# pan_tilt_laser_driver.net
KiCad netlist of a schematic drawn in EAGLE
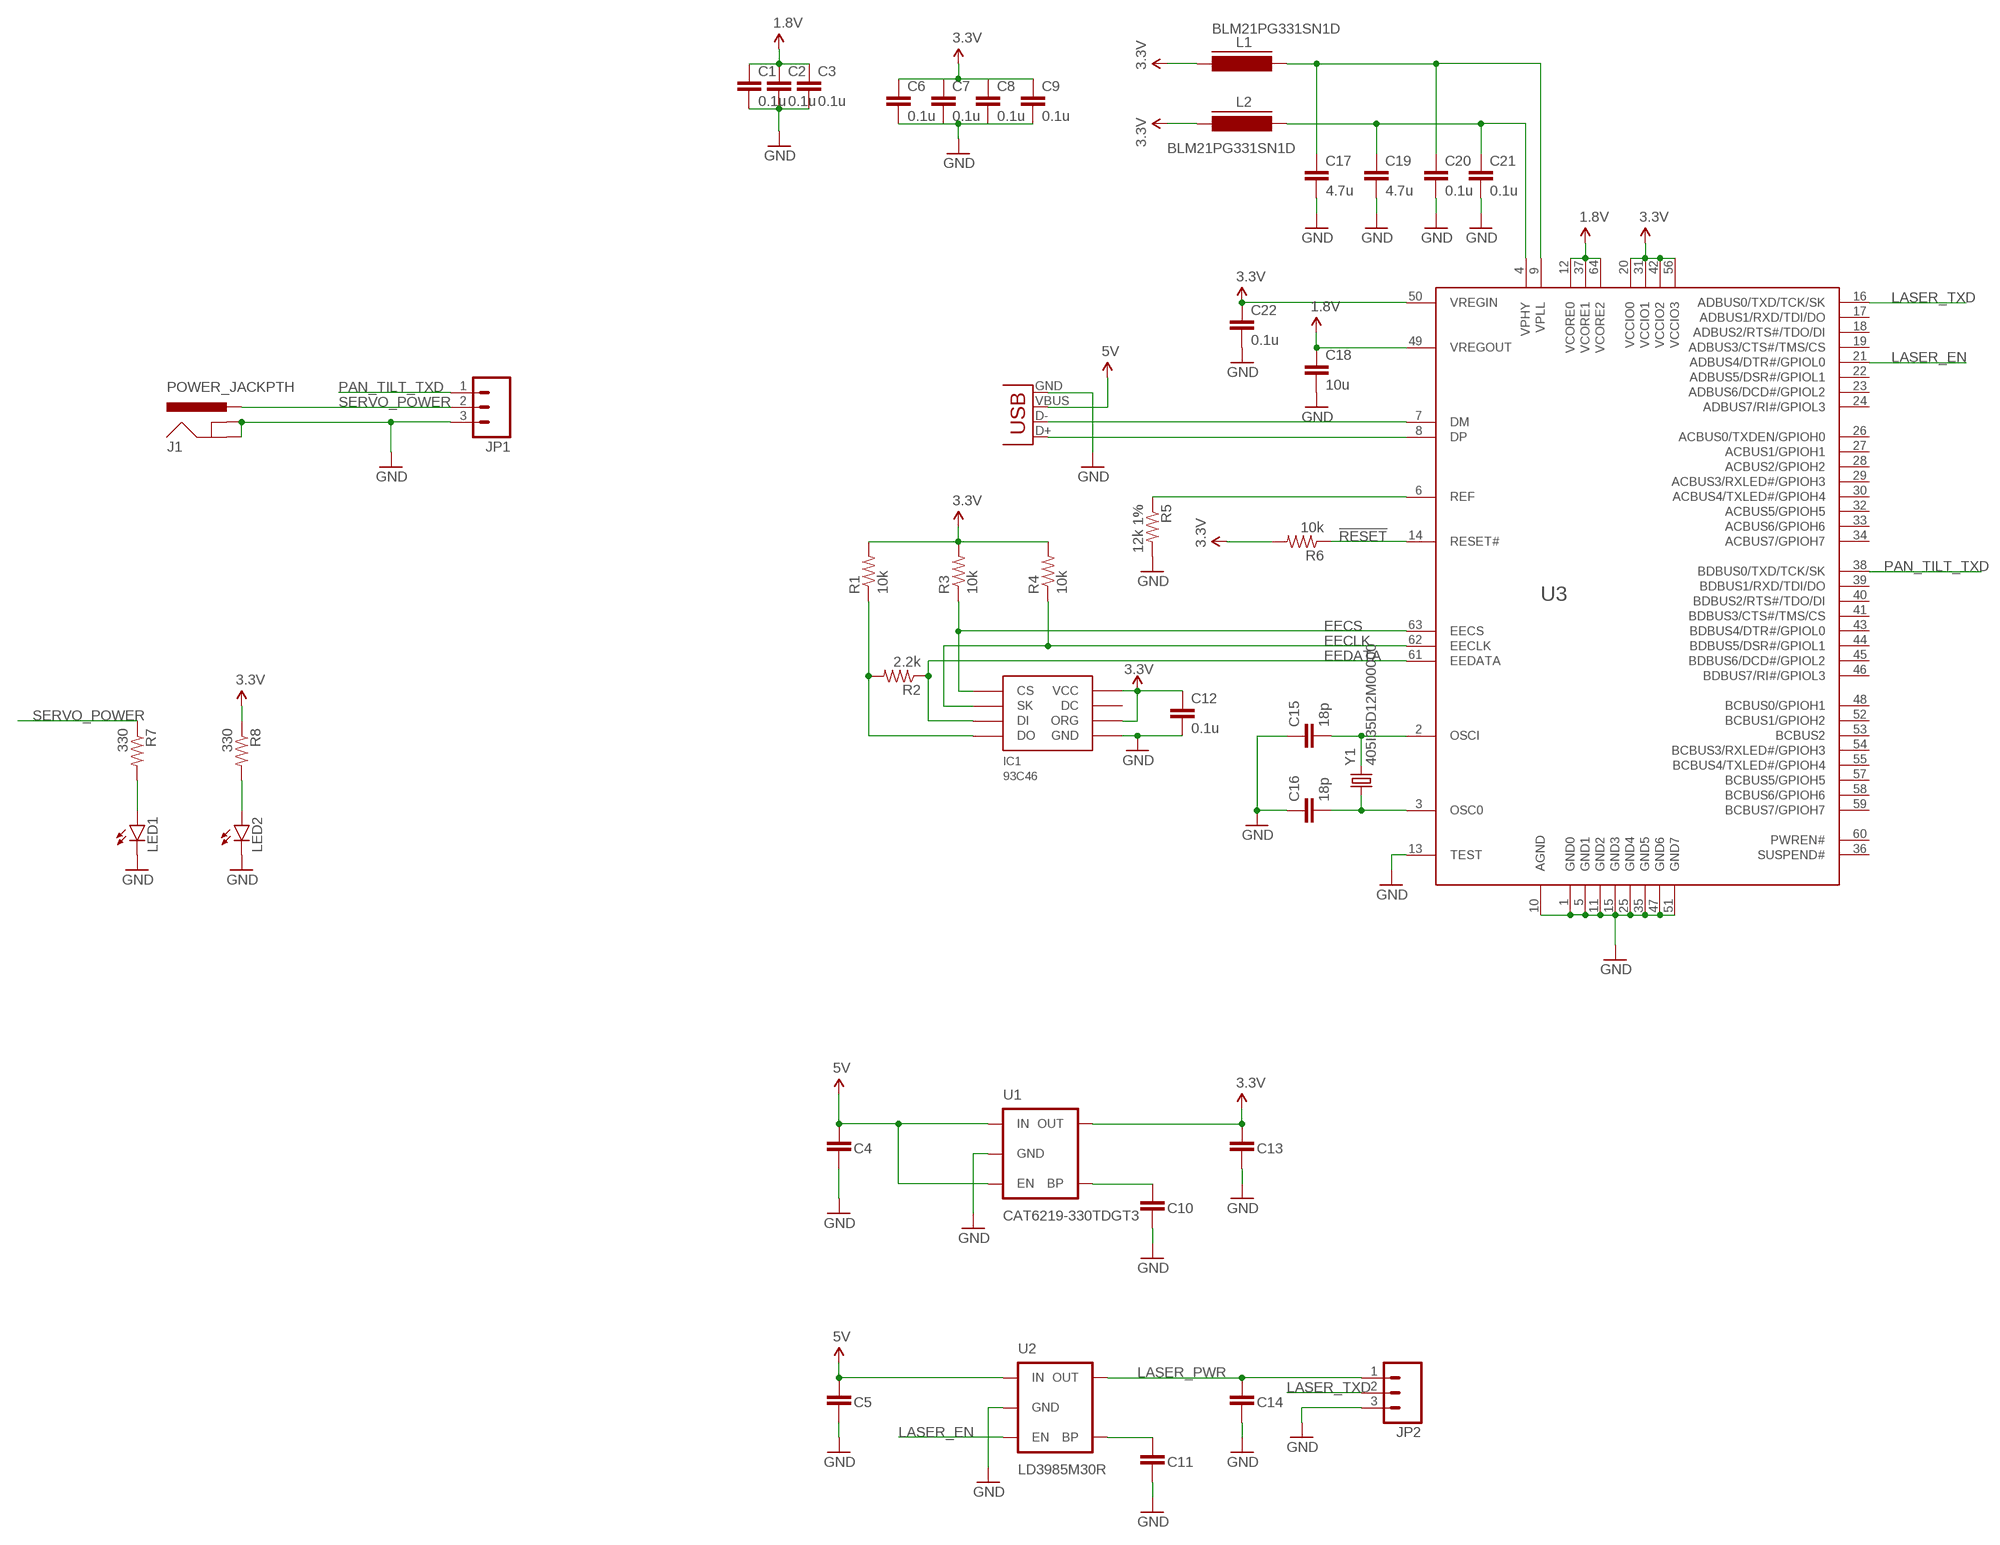
[diagram p0: schematic, sheet 1]

(export (version "E")
  (design (tool "Eeschema 10.0.6"))
  (components
    (comp (ref "C1")
      (value "0.1u")
      (footprint "eagle-import:C0603K")
      (libsource (lib "eagle-import") (part "C-EUC0603K"))
    )
    (comp (ref "C2")
      (value "0.1u")
      (footprint "eagle-import:C0603K")
      (libsource (lib "eagle-import") (part "C-EUC0603K"))
    )
    (comp (ref "C3")
      (value "0.1u")
      (footprint "eagle-import:C0603K")
      (libsource (lib "eagle-import") (part "C-EUC0603K"))
    )
    (comp (ref "C4")
      (value "10u")
      (footprint "eagle-import:0603-CAP")
      (libsource (lib "eagle-import") (part "CAP0603-CAP"))
    )
    (comp (ref "C5")
      (value "10u")
      (footprint "eagle-import:0603-CAP")
      (libsource (lib "eagle-import") (part "CAP0603-CAP"))
    )
    (comp (ref "C6")
      (value "0.1u")
      (footprint "eagle-import:C0603K")
      (libsource (lib "eagle-import") (part "C-EUC0603K"))
    )
    (comp (ref "C7")
      (value "0.1u")
      (footprint "eagle-import:C0603K")
      (libsource (lib "eagle-import") (part "C-EUC0603K"))
    )
    (comp (ref "C8")
      (value "0.1u")
      (footprint "eagle-import:C0603K")
      (libsource (lib "eagle-import") (part "C-EUC0603K"))
    )
    (comp (ref "C9")
      (value "0.1u")
      (footprint "eagle-import:C0603K")
      (libsource (lib "eagle-import") (part "C-EUC0603K"))
    )
    (comp (ref "C10")
      (value "0.01u")
      (footprint "eagle-import:0603-CAP")
      (libsource (lib "eagle-import") (part "CAP0603-CAP"))
    )
    (comp (ref "C11")
      (value "0.01u")
      (footprint "eagle-import:0603-CAP")
      (libsource (lib "eagle-import") (part "CAP0603-CAP"))
    )
    (comp (ref "C12")
      (value "0.1u")
      (footprint "eagle-import:C0603K")
      (libsource (lib "eagle-import") (part "C-EUC0603K"))
    )
    (comp (ref "C13")
      (value "10u")
      (footprint "eagle-import:0603-CAP")
      (libsource (lib "eagle-import") (part "CAP0603-CAP"))
    )
    (comp (ref "C14")
      (value "10u")
      (footprint "eagle-import:0603-CAP")
      (libsource (lib "eagle-import") (part "CAP0603-CAP"))
    )
    (comp (ref "C15")
      (value "18p")
      (footprint "eagle-import:C0603K")
      (libsource (lib "eagle-import") (part "C-EUC0603K"))
    )
    (comp (ref "C16")
      (value "18p")
      (footprint "eagle-import:C0603K")
      (libsource (lib "eagle-import") (part "C-EUC0603K"))
    )
    (comp (ref "C17")
      (value "4.7u")
      (footprint "eagle-import:C0603K")
      (libsource (lib "eagle-import") (part "C-EUC0603K"))
    )
    (comp (ref "C18")
      (value "10u")
      (footprint "eagle-import:C0603K")
      (libsource (lib "eagle-import") (part "C-EUC0603K"))
    )
    (comp (ref "C19")
      (value "4.7u")
      (footprint "eagle-import:C0603K")
      (libsource (lib "eagle-import") (part "C-EUC0603K"))
    )
    (comp (ref "C20")
      (value "0.1u")
      (footprint "eagle-import:C0603K")
      (libsource (lib "eagle-import") (part "C-EUC0603K"))
    )
    (comp (ref "C21")
      (value "0.1u")
      (footprint "eagle-import:C0603K")
      (libsource (lib "eagle-import") (part "C-EUC0603K"))
    )
    (comp (ref "C22")
      (value "0.1u")
      (footprint "eagle-import:C0603K")
      (libsource (lib "eagle-import") (part "C-EUC0603K"))
    )
    (comp (ref "IC1")
      (value "93C46")
      (footprint "eagle-import:SOIC8")
      (libsource (lib "eagle-import") (part "93C46"))
    )
    (comp (ref "J1")
      (value "POWER_JACKPTH")
      (footprint "eagle-import:POWER_JACK_PTH")
      (libsource (lib "eagle-import") (part "POWER_JACKPTH"))
    )
    (comp (ref "JP1")
      (value "M0322-03-5035")
      (footprint "eagle-import:22-03-5035")
      (libsource (lib "eagle-import") (part "M0322-03-5035"))
    )
    (comp (ref "JP2")
      (value "651-5442251")
      (footprint "eagle-import:SCREWTERMINAL-3.5MM-3")
      (libsource (lib "eagle-import") (part "M03SCREW"))
    )
    (comp (ref "L1")
      (value "BLM21PG331SN1D")
      (footprint "eagle-import:FB805")
      (libsource (lib "eagle-import") (part "FERRITE_BEAD805"))
    )
    (comp (ref "L2")
      (value "BLM21PG331SN1D")
      (footprint "eagle-import:FB805")
      (libsource (lib "eagle-import") (part "FERRITE_BEAD805"))
    )
    (comp (ref "LED1")
      (value "LED1206")
      (footprint "eagle-import:LED-1206")
      (libsource (lib "eagle-import") (part "LED1206"))
    )
    (comp (ref "LED2")
      (value "LED1206")
      (footprint "eagle-import:LED-1206")
      (libsource (lib "eagle-import") (part "LED1206"))
    )
    (comp (ref "R1")
      (value "10k")
      (footprint "eagle-import:R0603")
      (libsource (lib "eagle-import") (part "R-US_R0603"))
    )
    (comp (ref "R2")
      (value "2.2k")
      (footprint "eagle-import:R0603")
      (libsource (lib "eagle-import") (part "R-US_R0603"))
    )
    (comp (ref "R3")
      (value "10k")
      (footprint "eagle-import:R0603")
      (libsource (lib "eagle-import") (part "R-US_R0603"))
    )
    (comp (ref "R4")
      (value "10k")
      (footprint "eagle-import:R0603")
      (libsource (lib "eagle-import") (part "R-US_R0603"))
    )
    (comp (ref "R5")
      (value "12k 1%")
      (footprint "eagle-import:R0603")
      (libsource (lib "eagle-import") (part "R-US_R0603"))
    )
    (comp (ref "R6")
      (value "10k")
      (footprint "eagle-import:R0603")
      (libsource (lib "eagle-import") (part "R-US_R0603"))
    )
    (comp (ref "R7")
      (value "330")
      (footprint "eagle-import:R0603")
      (libsource (lib "eagle-import") (part "R-US_R0603"))
    )
    (comp (ref "R8")
      (value "330")
      (footprint "eagle-import:R0603")
      (libsource (lib "eagle-import") (part "R-US_R0603"))
    )
    (comp (ref "U1")
      (value "CAT6219-330TDGT3")
      (footprint "eagle-import:SOT23-5")
      (libsource (lib "eagle-import") (part "V_REG_MIC52195V"))
    )
    (comp (ref "U2")
      (value "LD3985M30R")
      (footprint "eagle-import:SOT23-5")
      (libsource (lib "eagle-import") (part "V_REG_MIC52195V"))
    )
    (comp (ref "U3")
      (value "FT2232H")
      (footprint "eagle-import:LQFP64")
      (libsource (lib "eagle-import") (part "FT2232H"))
    )
    (comp (ref "X1")
      (value "538-47346-0001")
      (footprint "eagle-import:USB-MICROB")
      (libsource (lib "eagle-import") (part "USB-MICROB"))
    )
    (comp (ref "Y1")
      (value "405I35D12M00000")
      (footprint "eagle-import:CRYSTAL-SMD-5X3")
      (libsource (lib "eagle-import") (part "CRYSTAL5X3"))
    )
  )
  (nets
    (net (code "1") (name "/EECLK") (class "Default")
      (node (ref "IC1") (pin "2") (pinfunction "SK_2") (pintype "bidirectional"))
      (node (ref "R4") (pin "1") (pinfunction "1_1") (pintype "passive"))
      (node (ref "U3") (pin "62") (pinfunction "EECLK_62") (pintype "bidirectional"))
    )
    (net (code "2") (name "/EECS") (class "Default")
      (node (ref "IC1") (pin "1") (pinfunction "CS_1") (pintype "bidirectional"))
      (node (ref "R3") (pin "1") (pinfunction "1_1") (pintype "passive"))
      (node (ref "U3") (pin "63") (pinfunction "EECS_63") (pintype "bidirectional"))
    )
    (net (code "3") (name "/EEDATA") (class "Default")
      (node (ref "IC1") (pin "3") (pinfunction "DI_3") (pintype "bidirectional"))
      (node (ref "R2") (pin "1") (pinfunction "1_1") (pintype "passive"))
      (node (ref "U3") (pin "61") (pinfunction "EEDATA_61") (pintype "bidirectional"))
    )
    (net (code "4") (name "/LASER_EN") (class "Default")
      (node (ref "U2") (pin "3") (pinfunction "EN_3") (pintype "input"))
      (node (ref "U3") (pin "21") (pinfunction "ADBUS4/DTR#/GPIOL0_21") (pintype "bidirectional"))
    )
    (net (code "5") (name "/LASER_PWR") (class "Default")
      (node (ref "C14") (pin "1") (pinfunction "1_1") (pintype "passive"))
      (node (ref "JP2") (pin "1") (pinfunction "1_1") (pintype "passive"))
      (node (ref "U2") (pin "5") (pinfunction "OUT_5") (pintype "passive"))
    )
    (net (code "6") (name "/LASER_TXD") (class "Default")
      (node (ref "JP2") (pin "2") (pinfunction "2_2") (pintype "passive"))
      (node (ref "U3") (pin "16") (pinfunction "ADBUS0/TXD/TCK/SK_16") (pintype "bidirectional"))
    )
    (net (code "7") (name "/PAN_TILT_TXD") (class "Default")
      (node (ref "JP1") (pin "1") (pinfunction "1_1") (pintype "passive"))
      (node (ref "U3") (pin "38") (pinfunction "BDBUS0/TXD/TCK/SK_38") (pintype "bidirectional"))
    )
    (net (code "8") (name "/SERVO_POWER") (class "Default")
      (node (ref "J1") (pin "PWR") (pinfunction "PWR_PWR") (pintype "bidirectional"))
      (node (ref "JP1") (pin "2") (pinfunction "2_2") (pintype "passive"))
      (node (ref "R7") (pin "1") (pinfunction "1_1") (pintype "passive"))
    )
    (net (code "9") (name "/~{RESET}") (class "Default")
      (node (ref "R6") (pin "1") (pinfunction "1_1") (pintype "passive"))
      (node (ref "U3") (pin "14") (pinfunction "RESET#_14") (pintype "bidirectional"))
    )
    (net (code "10") (name "1.8V") (class "Default")
      (node (ref "C1") (pin "1") (pinfunction "1_1") (pintype "passive"))
      (node (ref "C18") (pin "1") (pinfunction "1_1") (pintype "passive"))
      (node (ref "C2") (pin "1") (pinfunction "1_1") (pintype "passive"))
      (node (ref "C3") (pin "1") (pinfunction "1_1") (pintype "passive"))
      (node (ref "U3") (pin "12") (pinfunction "VCORE0_12") (pintype "bidirectional"))
      (node (ref "U3") (pin "37") (pinfunction "VCORE1_37") (pintype "bidirectional"))
      (node (ref "U3") (pin "49") (pinfunction "VREGOUT_49") (pintype "bidirectional"))
      (node (ref "U3") (pin "64") (pinfunction "VCORE2_64") (pintype "bidirectional"))
    )
    (net (code "11") (name "3.3V") (class "Default")
      (node (ref "C12") (pin "1") (pinfunction "1_1") (pintype "passive"))
      (node (ref "C13") (pin "1") (pinfunction "1_1") (pintype "passive"))
      (node (ref "C22") (pin "1") (pinfunction "1_1") (pintype "passive"))
      (node (ref "C6") (pin "1") (pinfunction "1_1") (pintype "passive"))
      (node (ref "C7") (pin "1") (pinfunction "1_1") (pintype "passive"))
      (node (ref "C8") (pin "1") (pinfunction "1_1") (pintype "passive"))
      (node (ref "C9") (pin "1") (pinfunction "1_1") (pintype "passive"))
      (node (ref "IC1") (pin "6") (pinfunction "ORG_6") (pintype "bidirectional"))
      (node (ref "IC1") (pin "8") (pinfunction "VCC_8") (pintype "bidirectional"))
      (node (ref "L1") (pin "2") (pinfunction "2_2") (pintype "passive"))
      (node (ref "L2") (pin "2") (pinfunction "2_2") (pintype "passive"))
      (node (ref "R1") (pin "2") (pinfunction "2_2") (pintype "passive"))
      (node (ref "R3") (pin "2") (pinfunction "2_2") (pintype "passive"))
      (node (ref "R4") (pin "2") (pinfunction "2_2") (pintype "passive"))
      (node (ref "R6") (pin "2") (pinfunction "2_2") (pintype "passive"))
      (node (ref "R8") (pin "1") (pinfunction "1_1") (pintype "passive"))
      (node (ref "U1") (pin "5") (pinfunction "OUT_5") (pintype "passive"))
      (node (ref "U3") (pin "20") (pinfunction "VCCIO0_20") (pintype "bidirectional"))
      (node (ref "U3") (pin "31") (pinfunction "VCCIO1_31") (pintype "bidirectional"))
      (node (ref "U3") (pin "42") (pinfunction "VCCIO2_42") (pintype "bidirectional"))
      (node (ref "U3") (pin "50") (pinfunction "VREGIN_50") (pintype "bidirectional"))
      (node (ref "U3") (pin "56") (pinfunction "VCCIO3_56") (pintype "bidirectional"))
    )
    (net (code "12") (name "5V") (class "Default")
      (node (ref "C4") (pin "1") (pinfunction "1_1") (pintype "passive"))
      (node (ref "C5") (pin "1") (pinfunction "1_1") (pintype "passive"))
      (node (ref "U1") (pin "1") (pinfunction "IN_1") (pintype "input"))
      (node (ref "U1") (pin "3") (pinfunction "EN_3") (pintype "input"))
      (node (ref "U2") (pin "1") (pinfunction "IN_1") (pintype "input"))
      (node (ref "X1") (pin "VBUS") (pinfunction "VBUS_VBUS") (pintype "bidirectional"))
    )
    (net (code "13") (name "GND") (class "Default")
      (node (ref "C1") (pin "2") (pinfunction "2_2") (pintype "passive"))
      (node (ref "C10") (pin "2") (pinfunction "2_2") (pintype "passive"))
      (node (ref "C11") (pin "2") (pinfunction "2_2") (pintype "passive"))
      (node (ref "C12") (pin "2") (pinfunction "2_2") (pintype "passive"))
      (node (ref "C13") (pin "2") (pinfunction "2_2") (pintype "passive"))
      (node (ref "C14") (pin "2") (pinfunction "2_2") (pintype "passive"))
      (node (ref "C15") (pin "1") (pinfunction "1_1") (pintype "passive"))
      (node (ref "C16") (pin "1") (pinfunction "1_1") (pintype "passive"))
      (node (ref "C17") (pin "2") (pinfunction "2_2") (pintype "passive"))
      (node (ref "C18") (pin "2") (pinfunction "2_2") (pintype "passive"))
      (node (ref "C19") (pin "2") (pinfunction "2_2") (pintype "passive"))
      (node (ref "C2") (pin "2") (pinfunction "2_2") (pintype "passive"))
      (node (ref "C20") (pin "2") (pinfunction "2_2") (pintype "passive"))
      (node (ref "C21") (pin "2") (pinfunction "2_2") (pintype "passive"))
      (node (ref "C22") (pin "2") (pinfunction "2_2") (pintype "passive"))
      (node (ref "C3") (pin "2") (pinfunction "2_2") (pintype "passive"))
      (node (ref "C4") (pin "2") (pinfunction "2_2") (pintype "passive"))
      (node (ref "C5") (pin "2") (pinfunction "2_2") (pintype "passive"))
      (node (ref "C6") (pin "2") (pinfunction "2_2") (pintype "passive"))
      (node (ref "C7") (pin "2") (pinfunction "2_2") (pintype "passive"))
      (node (ref "C8") (pin "2") (pinfunction "2_2") (pintype "passive"))
      (node (ref "C9") (pin "2") (pinfunction "2_2") (pintype "passive"))
      (node (ref "IC1") (pin "5") (pinfunction "GND_5") (pintype "bidirectional"))
      (node (ref "J1") (pin "GND") (pinfunction "GND_GND") (pintype "bidirectional"))
      (node (ref "J1") (pin "GNDBREAK") (pinfunction "GNDBREAK_GNDBREAK") (pintype "bidirectional"))
      (node (ref "JP1") (pin "3") (pinfunction "3_3") (pintype "passive"))
      (node (ref "JP2") (pin "3") (pinfunction "3_3") (pintype "passive"))
      (node (ref "LED1") (pin "C") (pinfunction "C_C") (pintype "passive"))
      (node (ref "LED2") (pin "C") (pinfunction "C_C") (pintype "passive"))
      (node (ref "R5") (pin "2") (pinfunction "2_2") (pintype "passive"))
      (node (ref "U1") (pin "2") (pinfunction "GND_2") (pintype "input"))
      (node (ref "U2") (pin "2") (pinfunction "GND_2") (pintype "input"))
      (node (ref "U3") (pin "1") (pinfunction "GND0_1") (pintype "bidirectional"))
      (node (ref "U3") (pin "10") (pinfunction "AGND_10") (pintype "bidirectional"))
      (node (ref "U3") (pin "11") (pinfunction "GND2_11") (pintype "bidirectional"))
      (node (ref "U3") (pin "13") (pinfunction "TEST_13") (pintype "bidirectional"))
      (node (ref "U3") (pin "15") (pinfunction "GND3_15") (pintype "bidirectional"))
      (node (ref "U3") (pin "25") (pinfunction "GND4_25") (pintype "bidirectional"))
      (node (ref "U3") (pin "35") (pinfunction "GND5_35") (pintype "bidirectional"))
      (node (ref "U3") (pin "47") (pinfunction "GND6_47") (pintype "bidirectional"))
      (node (ref "U3") (pin "5") (pinfunction "GND1_5") (pintype "bidirectional"))
      (node (ref "U3") (pin "51") (pinfunction "GND7_51") (pintype "bidirectional"))
      (node (ref "X1") (pin "GND") (pinfunction "GND_GND") (pintype "bidirectional"))
    )
    (net (code "14") (name "Net-(IC1-DO)") (class "Default")
      (node (ref "IC1") (pin "4") (pinfunction "DO_4") (pintype "bidirectional"))
      (node (ref "R1") (pin "1") (pinfunction "1_1") (pintype "passive"))
      (node (ref "R2") (pin "2") (pinfunction "2_2") (pintype "passive"))
    )
    (net (code "15") (name "Net-(LED1-PadA)") (class "Default")
      (node (ref "LED1") (pin "A") (pinfunction "A_A") (pintype "passive"))
      (node (ref "R7") (pin "2") (pinfunction "2_2") (pintype "passive"))
    )
    (net (code "16") (name "Net-(LED2-PadA)") (class "Default")
      (node (ref "LED2") (pin "A") (pinfunction "A_A") (pintype "passive"))
      (node (ref "R8") (pin "2") (pinfunction "2_2") (pintype "passive"))
    )
    (net (code "17") (name "Net-(U1-BP)") (class "Default")
      (node (ref "C10") (pin "1") (pinfunction "1_1") (pintype "passive"))
      (node (ref "U1") (pin "4") (pinfunction "BP_4") (pintype "input"))
    )
    (net (code "18") (name "Net-(U2-BP)") (class "Default")
      (node (ref "C11") (pin "1") (pinfunction "1_1") (pintype "passive"))
      (node (ref "U2") (pin "4") (pinfunction "BP_4") (pintype "input"))
    )
    (net (code "19") (name "Net-(U3-DM)") (class "Default")
      (node (ref "U3") (pin "7") (pinfunction "DM_7") (pintype "bidirectional"))
      (node (ref "X1") (pin "D-") (pinfunction "D-_D-") (pintype "bidirectional"))
    )
    (net (code "20") (name "Net-(U3-DP)") (class "Default")
      (node (ref "U3") (pin "8") (pinfunction "DP_8") (pintype "bidirectional"))
      (node (ref "X1") (pin "D+") (pinfunction "D+_D+") (pintype "bidirectional"))
    )
    (net (code "21") (name "Net-(U3-OSC0)") (class "Default")
      (node (ref "C16") (pin "2") (pinfunction "2_2") (pintype "passive"))
      (node (ref "U3") (pin "3") (pinfunction "OSC0_3") (pintype "bidirectional"))
      (node (ref "Y1") (pin "1") (pinfunction "1_1") (pintype "passive"))
    )
    (net (code "22") (name "Net-(U3-OSCI)") (class "Default")
      (node (ref "C15") (pin "2") (pinfunction "2_2") (pintype "passive"))
      (node (ref "U3") (pin "2") (pinfunction "OSCI_2") (pintype "bidirectional"))
      (node (ref "Y1") (pin "3") (pinfunction "2_3") (pintype "passive"))
    )
    (net (code "23") (name "Net-(U3-REF)") (class "Default")
      (node (ref "R5") (pin "1") (pinfunction "1_1") (pintype "passive"))
      (node (ref "U3") (pin "6") (pinfunction "REF_6") (pintype "bidirectional"))
    )
    (net (code "24") (name "Net-(U3-VPHY)") (class "Default")
      (node (ref "C19") (pin "1") (pinfunction "1_1") (pintype "passive"))
      (node (ref "C21") (pin "1") (pinfunction "1_1") (pintype "passive"))
      (node (ref "L2") (pin "1") (pinfunction "1_1") (pintype "passive"))
      (node (ref "U3") (pin "4") (pinfunction "VPHY_4") (pintype "bidirectional"))
    )
    (net (code "25") (name "Net-(U3-VPLL)") (class "Default")
      (node (ref "C17") (pin "1") (pinfunction "1_1") (pintype "passive"))
      (node (ref "C20") (pin "1") (pinfunction "1_1") (pintype "passive"))
      (node (ref "L1") (pin "1") (pinfunction "1_1") (pintype "passive"))
      (node (ref "U3") (pin "9") (pinfunction "VPLL_9") (pintype "bidirectional"))
    )
    (net (code "26") (name "unconnected-(IC1-DC-Pad7)") (class "Default")
      (node (ref "IC1") (pin "7") (pinfunction "DC_7") (pintype "bidirectional"))
    )
    (net (code "27") (name "unconnected-(U3-ACBUS0{slash}TXDEN{slash}GPIOH0-Pad26)") (class "Default")
      (node (ref "U3") (pin "26") (pinfunction "ACBUS0/TXDEN/GPIOH0_26") (pintype "bidirectional"))
    )
    (net (code "28") (name "unconnected-(U3-ACBUS1{slash}GPIOH1-Pad27)") (class "Default")
      (node (ref "U3") (pin "27") (pinfunction "ACBUS1/GPIOH1_27") (pintype "bidirectional"))
    )
    (net (code "29") (name "unconnected-(U3-ACBUS2{slash}GPIOH2-Pad28)") (class "Default")
      (node (ref "U3") (pin "28") (pinfunction "ACBUS2/GPIOH2_28") (pintype "bidirectional"))
    )
    (net (code "30") (name "unconnected-(U3-ACBUS3{slash}RXLED#{slash}GPIOH3-Pad29)") (class "Default")
      (node (ref "U3") (pin "29") (pinfunction "ACBUS3/RXLED#/GPIOH3_29") (pintype "bidirectional"))
    )
    (net (code "31") (name "unconnected-(U3-ACBUS4{slash}TXLED#{slash}GPIOH4-Pad30)") (class "Default")
      (node (ref "U3") (pin "30") (pinfunction "ACBUS4/TXLED#/GPIOH4_30") (pintype "bidirectional"))
    )
    (net (code "32") (name "unconnected-(U3-ACBUS5{slash}GPIOH5-Pad32)") (class "Default")
      (node (ref "U3") (pin "32") (pinfunction "ACBUS5/GPIOH5_32") (pintype "bidirectional"))
    )
    (net (code "33") (name "unconnected-(U3-ACBUS6{slash}GPIOH6-Pad33)") (class "Default")
      (node (ref "U3") (pin "33") (pinfunction "ACBUS6/GPIOH6_33") (pintype "bidirectional"))
    )
    (net (code "34") (name "unconnected-(U3-ACBUS7{slash}GPIOH7-Pad34)") (class "Default")
      (node (ref "U3") (pin "34") (pinfunction "ACBUS7/GPIOH7_34") (pintype "bidirectional"))
    )
    (net (code "35") (name "unconnected-(U3-ADBUS1{slash}RXD{slash}TDI{slash}DO-Pad17)") (class "Default")
      (node (ref "U3") (pin "17") (pinfunction "ADBUS1/RXD/TDI/DO_17") (pintype "bidirectional"))
    )
    (net (code "36") (name "unconnected-(U3-ADBUS2{slash}RTS#{slash}TDO{slash}DI-Pad18)") (class "Default")
      (node (ref "U3") (pin "18") (pinfunction "ADBUS2/RTS#/TDO/DI_18") (pintype "bidirectional"))
    )
    (net (code "37") (name "unconnected-(U3-ADBUS3{slash}CTS#{slash}TMS{slash}CS-Pad19)") (class "Default")
      (node (ref "U3") (pin "19") (pinfunction "ADBUS3/CTS#/TMS/CS_19") (pintype "bidirectional"))
    )
    (net (code "38") (name "unconnected-(U3-ADBUS5{slash}DSR#{slash}GPIOL1-Pad22)") (class "Default")
      (node (ref "U3") (pin "22") (pinfunction "ADBUS5/DSR#/GPIOL1_22") (pintype "bidirectional"))
    )
    (net (code "39") (name "unconnected-(U3-ADBUS6{slash}DCD#{slash}GPIOL2-Pad23)") (class "Default")
      (node (ref "U3") (pin "23") (pinfunction "ADBUS6/DCD#/GPIOL2_23") (pintype "bidirectional"))
    )
    (net (code "40") (name "unconnected-(U3-ADBUS7{slash}RI#{slash}GPIOL3-Pad24)") (class "Default")
      (node (ref "U3") (pin "24") (pinfunction "ADBUS7/RI#/GPIOL3_24") (pintype "bidirectional"))
    )
    (net (code "41") (name "unconnected-(U3-BCBUS0{slash}GPIOH1-Pad48)") (class "Default")
      (node (ref "U3") (pin "48") (pinfunction "BCBUS0/GPIOH1_48") (pintype "bidirectional"))
    )
    (net (code "42") (name "unconnected-(U3-BCBUS1{slash}GPIOH2-Pad52)") (class "Default")
      (node (ref "U3") (pin "52") (pinfunction "BCBUS1/GPIOH2_52") (pintype "bidirectional"))
    )
    (net (code "43") (name "unconnected-(U3-BCBUS2-Pad53)") (class "Default")
      (node (ref "U3") (pin "53") (pinfunction "BCBUS2_53") (pintype "bidirectional"))
    )
    (net (code "44") (name "unconnected-(U3-BCBUS3{slash}RXLED#{slash}GPIOH3-Pad54)") (class "Default")
      (node (ref "U3") (pin "54") (pinfunction "BCBUS3/RXLED#/GPIOH3_54") (pintype "bidirectional"))
    )
    (net (code "45") (name "unconnected-(U3-BCBUS4{slash}TXLED#{slash}GPIOH4-Pad55)") (class "Default")
      (node (ref "U3") (pin "55") (pinfunction "BCBUS4/TXLED#/GPIOH4_55") (pintype "bidirectional"))
    )
    (net (code "46") (name "unconnected-(U3-BCBUS5{slash}GPIOH5-Pad57)") (class "Default")
      (node (ref "U3") (pin "57") (pinfunction "BCBUS5/GPIOH5_57") (pintype "bidirectional"))
    )
    (net (code "47") (name "unconnected-(U3-BCBUS6{slash}GPIOH6-Pad58)") (class "Default")
      (node (ref "U3") (pin "58") (pinfunction "BCBUS6/GPIOH6_58") (pintype "bidirectional"))
    )
    (net (code "48") (name "unconnected-(U3-BCBUS7{slash}GPIOH7-Pad59)") (class "Default")
      (node (ref "U3") (pin "59") (pinfunction "BCBUS7/GPIOH7_59") (pintype "bidirectional"))
    )
    (net (code "49") (name "unconnected-(U3-BDBUS1{slash}RXD{slash}TDI{slash}DO-Pad39)") (class "Default")
      (node (ref "U3") (pin "39") (pinfunction "BDBUS1/RXD/TDI/DO_39") (pintype "bidirectional"))
    )
    (net (code "50") (name "unconnected-(U3-BDBUS2{slash}RTS#{slash}TDO{slash}DI-Pad40)") (class "Default")
      (node (ref "U3") (pin "40") (pinfunction "BDBUS2/RTS#/TDO/DI_40") (pintype "bidirectional"))
    )
    (net (code "51") (name "unconnected-(U3-BDBUS3{slash}CTS#{slash}TMS{slash}CS-Pad41)") (class "Default")
      (node (ref "U3") (pin "41") (pinfunction "BDBUS3/CTS#/TMS/CS_41") (pintype "bidirectional"))
    )
    (net (code "52") (name "unconnected-(U3-BDBUS4{slash}DTR#{slash}GPIOL0-Pad43)") (class "Default")
      (node (ref "U3") (pin "43") (pinfunction "BDBUS4/DTR#/GPIOL0_43") (pintype "bidirectional"))
    )
    (net (code "53") (name "unconnected-(U3-BDBUS5{slash}DSR#{slash}GPIOL1-Pad44)") (class "Default")
      (node (ref "U3") (pin "44") (pinfunction "BDBUS5/DSR#/GPIOL1_44") (pintype "bidirectional"))
    )
    (net (code "54") (name "unconnected-(U3-BDBUS6{slash}DCD#{slash}GPIOL2-Pad45)") (class "Default")
      (node (ref "U3") (pin "45") (pinfunction "BDBUS6/DCD#/GPIOL2_45") (pintype "bidirectional"))
    )
    (net (code "55") (name "unconnected-(U3-BDBUS7{slash}RI#{slash}GPIOL3-Pad46)") (class "Default")
      (node (ref "U3") (pin "46") (pinfunction "BDBUS7/RI#/GPIOL3_46") (pintype "bidirectional"))
    )
    (net (code "56") (name "unconnected-(U3-PWREN#-Pad60)") (class "Default")
      (node (ref "U3") (pin "60") (pinfunction "PWREN#_60") (pintype "bidirectional"))
    )
    (net (code "57") (name "unconnected-(U3-SUSPEND#-Pad36)") (class "Default")
      (node (ref "U3") (pin "36") (pinfunction "SUSPEND#_36") (pintype "bidirectional"))
    )
  )
)
